# H-00488_-_Card_Slot_Master.net
KiCad netlist of a schematic drawn in Altium Designer
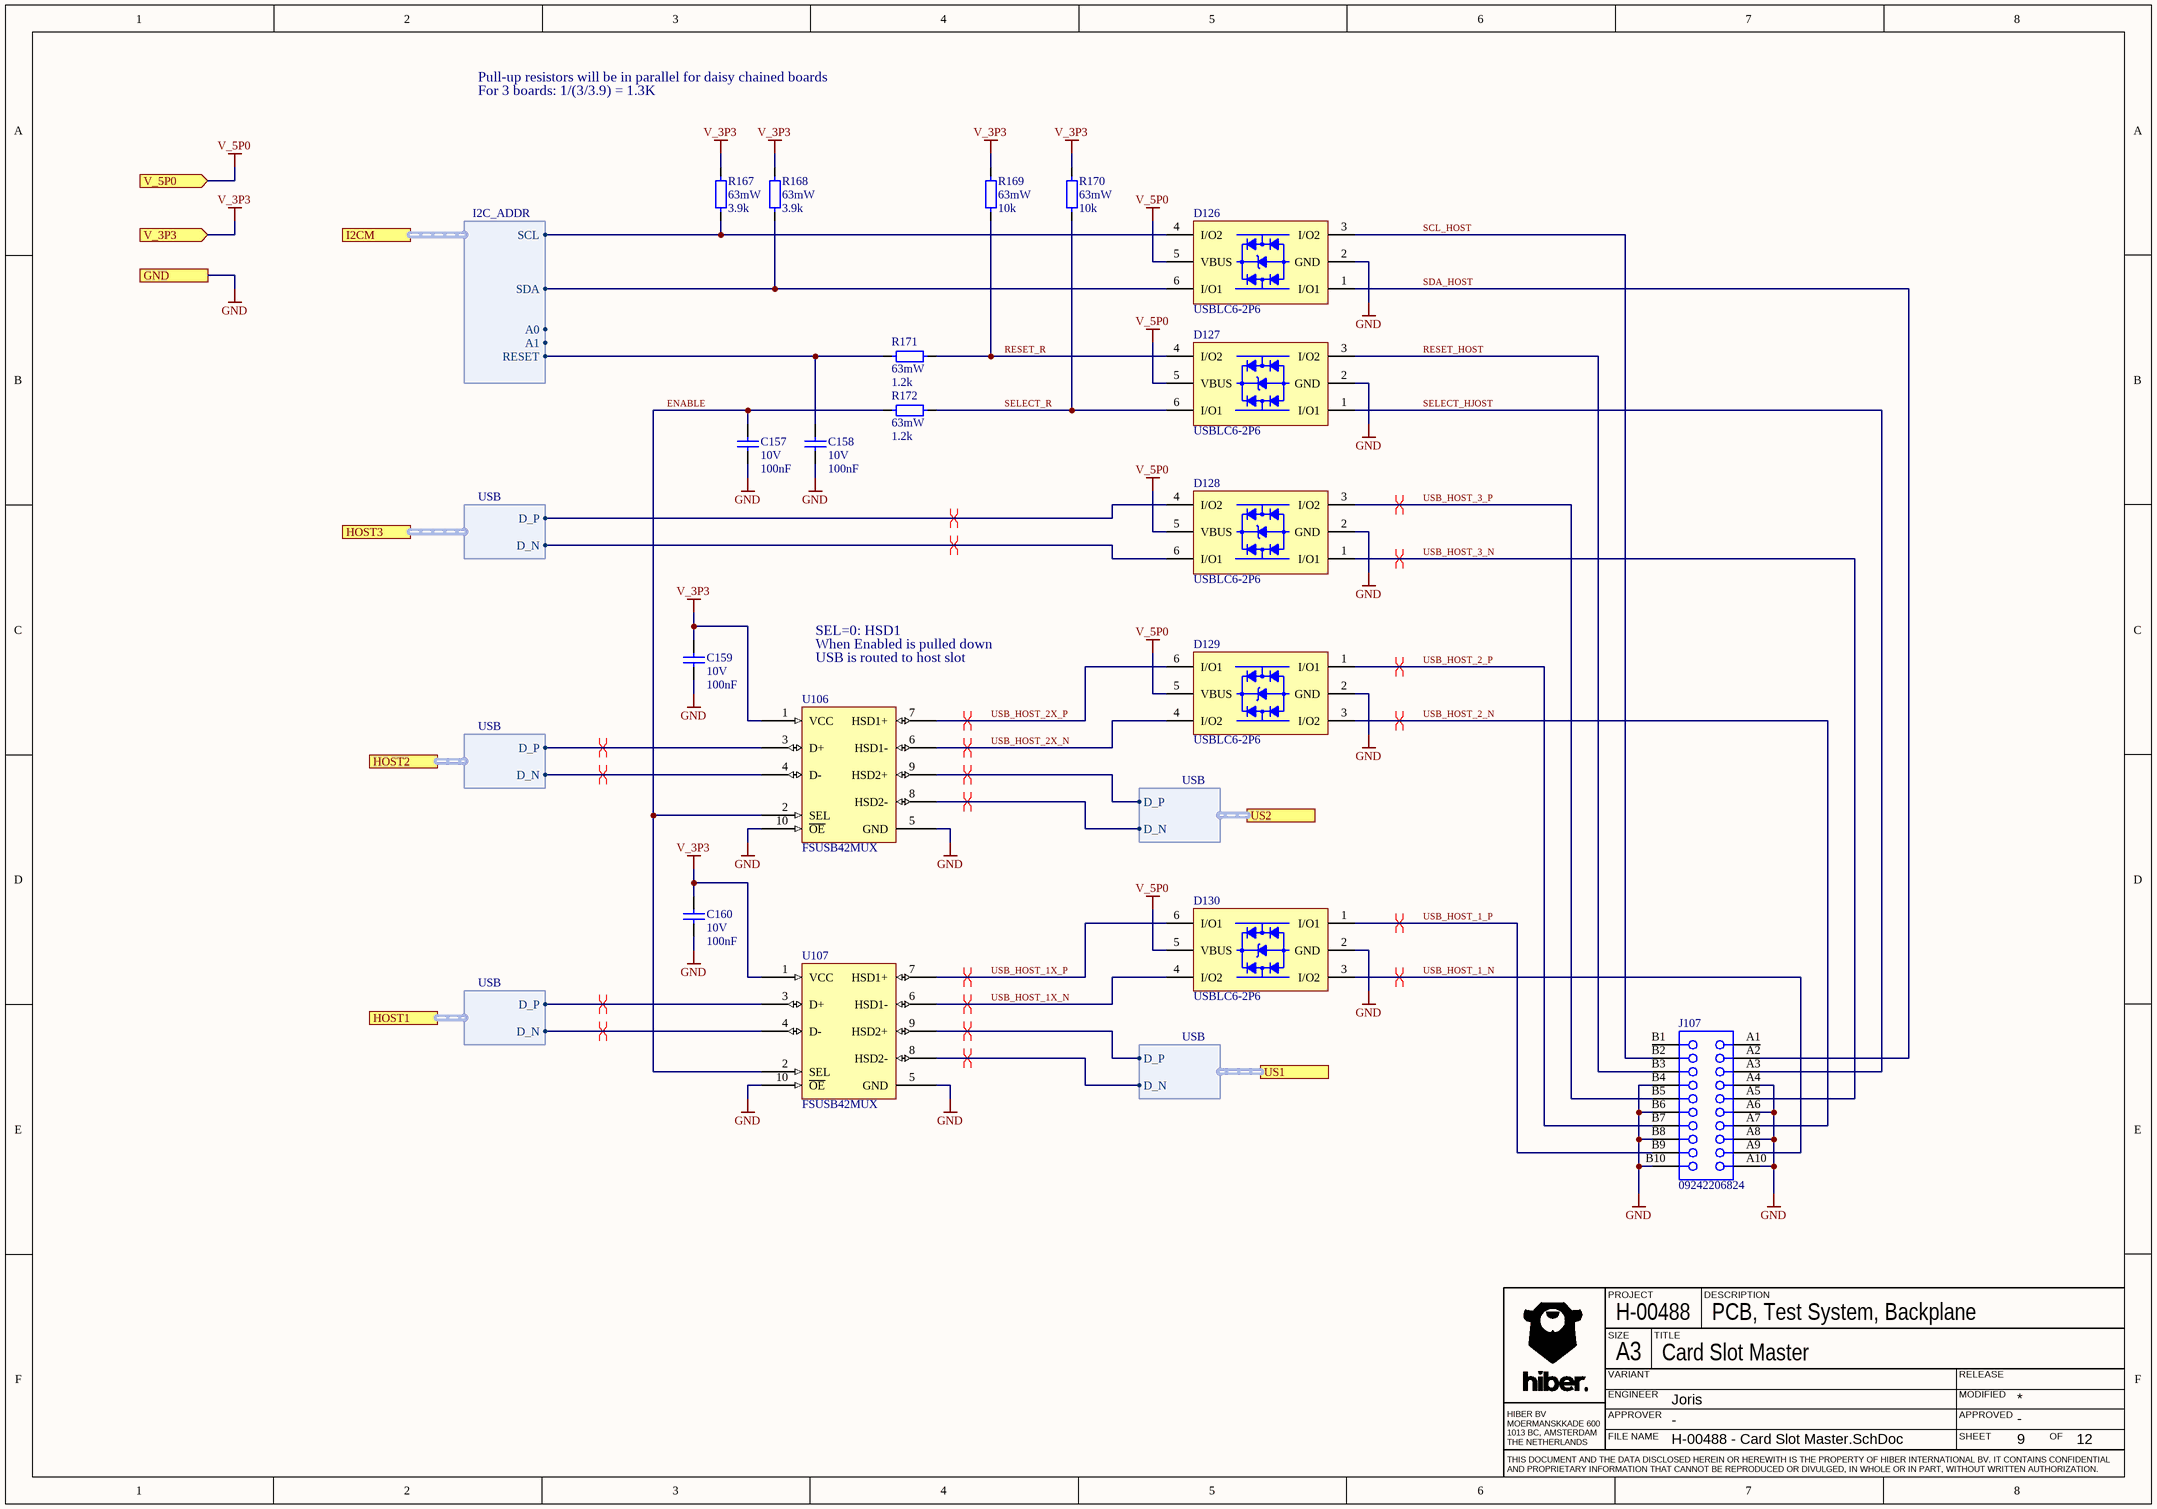
[diagram p0: H-00488 - Card Slot Master.SchDoc]

(export (version "E")
  (design (tool "Eeschema 10.0.6"))
  (components
    (comp (ref "C157")
      (value "100nF")
      (footprint "CAPC100X50X55L30N")
      (description "CAP Standard 0402 (1005) 100,0nF 10V X7R (Standard)")
      (fields
        (field (name "RATED VOLTAGE") "10V")
        (field (name "TOLERANCE") "10%")
        (field (name "Comment") "C0402C104K8RACTU")
      )
      (libsource (lib "Hiber Vault") (part "CAPACITOR"))
    )
    (comp (ref "C158")
      (value "100nF")
      (footprint "CAPC100X50X55L30N")
      (description "CAP Standard 0402 (1005) 100,0nF 10V X7R (Standard)")
      (fields
        (field (name "RATED VOLTAGE") "10V")
        (field (name "TOLERANCE") "10%")
        (field (name "Comment") "C0402C104K8RACTU")
      )
      (libsource (lib "Hiber Vault") (part "CAPACITOR"))
    )
    (comp (ref "C159")
      (value "100nF")
      (footprint "CAPC100X50X55L30N")
      (description "CAP Standard 0402 (1005) 100,0nF 10V X7R (Standard)")
      (fields
        (field (name "RATED VOLTAGE") "10V")
        (field (name "TOLERANCE") "10%")
        (field (name "Comment") "C0402C104K8RACTU")
      )
      (libsource (lib "Hiber Vault") (part "CAPACITOR"))
    )
    (comp (ref "C160")
      (value "100nF")
      (footprint "CAPC100X50X55L30N")
      (description "CAP Standard 0402 (1005) 100,0nF 10V X7R (Standard)")
      (fields
        (field (name "RATED VOLTAGE") "10V")
        (field (name "TOLERANCE") "10%")
        (field (name "Comment") "C0402C104K8RACTU")
      )
      (libsource (lib "Hiber Vault") (part "CAPACITOR"))
    )
    (comp (ref "D126")
      (value "USBLC6-2P6")
      (footprint "DIOSOFL6P50_160X160X95L29X26")
      (description "TVS DIODE 5.25VWM 17VC SOT666")
      (libsource (lib "Hiber") (part "ST_USBLC6-2"))
    )
    (comp (ref "D127")
      (value "USBLC6-2P6")
      (footprint "DIOSOFL6P50_160X160X95L29X26")
      (description "TVS DIODE 5.25VWM 17VC SOT666")
      (libsource (lib "Hiber") (part "ST_USBLC6-2"))
    )
    (comp (ref "D128")
      (value "USBLC6-2P6")
      (footprint "DIOSOFL6P50_160X160X95L29X26")
      (description "TVS DIODE 5.25VWM 17VC SOT666")
      (libsource (lib "Hiber") (part "ST_USBLC6-2"))
    )
    (comp (ref "D129")
      (value "USBLC6-2P6")
      (footprint "DIOSOFL6P50_160X160X95L29X26")
      (description "TVS DIODE 5.25VWM 17VC SOT666")
      (libsource (lib "") (part "ST_USBLC6-2_1"))
    )
    (comp (ref "D130")
      (value "USBLC6-2P6")
      (footprint "DIOSOFL6P50_160X160X95L29X26")
      (description "TVS DIODE 5.25VWM 17VC SOT666")
      (libsource (lib "") (part "ST_USBLC6-2_1"))
    )
    (comp (ref "J107")
      (value "09242206824")
      (footprint "HARTING_09242206824")
      (description "Board Euro Connector")
      (libsource (lib "Hiber") (part "DIN41612-3B-FEMALE"))
    )
    (comp (ref "R167")
      (value "3.9k")
      (footprint "RESC100X50X40L25N")
      (description "RES Standard Thick Film 0402 3K90 ±1% 0,063W")
      (fields
        (field (name "TOLERANCE") "1%")
        (field (name "RATED POWER") "63mW")
        (field (name "Comment") "CRCW04023K90FKED")
      )
      (libsource (lib "Hiber") (part "RESISTOR-2P"))
    )
    (comp (ref "R168")
      (value "3.9k")
      (footprint "RESC100X50X40L25N")
      (description "RES Standard Thick Film 0402 3K90 ±1% 0,063W")
      (fields
        (field (name "TOLERANCE") "1%")
        (field (name "RATED POWER") "63mW")
        (field (name "Comment") "CRCW04023K90FKED")
      )
      (libsource (lib "Hiber") (part "RESISTOR-2P"))
    )
    (comp (ref "R169")
      (value "10k")
      (footprint "RESC100X50X40L25N")
      (description "RES Standard Thick Film 0402 10K0 ±1% 0,063W")
      (fields
        (field (name "TOLERANCE") "1%")
        (field (name "RATED POWER") "63mW")
        (field (name "Comment") "CRCW040210K0FKED")
      )
      (libsource (lib "Hiber") (part "RESISTOR-2P"))
    )
    (comp (ref "R170")
      (value "10k")
      (footprint "RESC100X50X40L25N")
      (description "RES Standard Thick Film 0402 10K0 ±1% 0,063W")
      (fields
        (field (name "TOLERANCE") "1%")
        (field (name "RATED POWER") "63mW")
        (field (name "Comment") "CRCW040210K0FKED")
      )
      (libsource (lib "Hiber") (part "RESISTOR-2P"))
    )
    (comp (ref "R171")
      (value "1.2k")
      (footprint "RESC100X50X40L25N")
      (description "RES Standard Thick Film 0402 1K20 ±1% 0,063W")
      (fields
        (field (name "TOLERANCE") "1%")
        (field (name "RATED POWER") "63mW")
        (field (name "Comment") "CRCW04021K20FKED")
      )
      (libsource (lib "Hiber") (part "RESISTOR-2P"))
    )
    (comp (ref "R172")
      (value "1.2k")
      (footprint "RESC100X50X40L25N")
      (description "RES Standard Thick Film 0402 1K20 ±1% 0,063W")
      (fields
        (field (name "TOLERANCE") "1%")
        (field (name "RATED POWER") "63mW")
        (field (name "Comment") "CRCW04021K20FKED")
      )
      (libsource (lib "Hiber") (part "RESISTOR-2P"))
    )
    (comp (ref "U106")
      (value "FSUSB42MUX")
      (footprint "SOP10P50_300X490X110L55X25")
      (description "IC USB SWITCH DPDT 10MSOP")
      (fields (field (name "VOLTAGE") "4.3V"))
      (libsource (lib "Hiber") (part "FSUSB42MUX"))
    )
    (comp (ref "U107")
      (value "FSUSB42MUX")
      (footprint "SOP10P50_300X490X110L55X25")
      (description "IC USB SWITCH DPDT 10MSOP")
      (fields (field (name "VOLTAGE") "4.3V"))
      (libsource (lib "Hiber") (part "FSUSB42MUX"))
    )
  )
  (nets
    (net (code "3") (name "/ENABLE") (class "Default")
      (node (ref "C157") (pin "1") (pinfunction "1_1") (pintype "passive"))
      (node (ref "R172") (pin "2") (pinfunction "2_2") (pintype "passive"))
      (node (ref "U106") (pin "2") (pinfunction "SEL_2") (pintype "input"))
      (node (ref "U107") (pin "2") (pinfunction "SEL_2") (pintype "input"))
    )
    (net (code "4") (name "/RESET") (class "Default")
      (node (ref "C158") (pin "1") (pinfunction "1_1") (pintype "passive"))
      (node (ref "R171") (pin "2") (pinfunction "2_2") (pintype "passive"))
    )
    (net (code "5") (name "/RESET_HOST") (class "Default")
      (node (ref "D127") (pin "3") (pinfunction "I/O2_3") (pintype "passive"))
      (node (ref "J107") (pin "B3") (pinfunction "B3_B3") (pintype "passive"))
    )
    (net (code "6") (name "/RESET_R") (class "Default")
      (node (ref "D127") (pin "4") (pinfunction "I/O2_4") (pintype "passive"))
      (node (ref "R169") (pin "1") (pinfunction "1_1") (pintype "passive"))
      (node (ref "R171") (pin "1") (pinfunction "1_1") (pintype "passive"))
    )
    (net (code "7") (name "/SCL") (class "Default")
      (node (ref "D126") (pin "4") (pinfunction "I/O2_4") (pintype "passive"))
      (node (ref "R167") (pin "1") (pinfunction "1_1") (pintype "passive"))
    )
    (net (code "8") (name "/SCL_HOST") (class "Default")
      (node (ref "D126") (pin "3") (pinfunction "I/O2_3") (pintype "passive"))
      (node (ref "J107") (pin "B2") (pinfunction "B2_B2") (pintype "passive"))
    )
    (net (code "9") (name "/SDA") (class "Default")
      (node (ref "D126") (pin "6") (pinfunction "I/O1_6") (pintype "passive"))
      (node (ref "R168") (pin "1") (pinfunction "1_1") (pintype "passive"))
    )
    (net (code "10") (name "/SDA_HOST") (class "Default")
      (node (ref "D126") (pin "1") (pinfunction "I/O1_1") (pintype "passive"))
      (node (ref "J107") (pin "A2") (pinfunction "A2_A2") (pintype "passive"))
    )
    (net (code "11") (name "/SELECT_HJOST") (class "Default")
      (node (ref "D127") (pin "1") (pinfunction "I/O1_1") (pintype "passive"))
      (node (ref "J107") (pin "A3") (pinfunction "A3_A3") (pintype "passive"))
    )
    (net (code "12") (name "/SELECT_R") (class "Default")
      (node (ref "D127") (pin "6") (pinfunction "I/O1_6") (pintype "passive"))
      (node (ref "R170") (pin "1") (pinfunction "1_1") (pintype "passive"))
      (node (ref "R172") (pin "1") (pinfunction "1_1") (pintype "passive"))
    )
    (net (code "13") (name "/USB_HOST_1X_N") (class "Default")
      (node (ref "D130") (pin "4") (pinfunction "I/O2_4") (pintype "passive"))
      (node (ref "U107") (pin "6") (pinfunction "HSD1-_6") (pintype "bidirectional"))
    )
    (net (code "14") (name "/USB_HOST_1X_P") (class "Default")
      (node (ref "D130") (pin "6") (pinfunction "I/O1_6") (pintype "passive"))
      (node (ref "U107") (pin "7") (pinfunction "HSD1+_7") (pintype "bidirectional"))
    )
    (net (code "15") (name "/USB_HOST_1_N") (class "Default")
      (node (ref "D130") (pin "3") (pinfunction "I/O2_3") (pintype "passive"))
      (node (ref "J107") (pin "A9") (pinfunction "A9_A9") (pintype "passive"))
    )
    (net (code "16") (name "/USB_HOST_1_P") (class "Default")
      (node (ref "D130") (pin "1") (pinfunction "I/O1_1") (pintype "passive"))
      (node (ref "J107") (pin "B9") (pinfunction "B9_B9") (pintype "passive"))
    )
    (net (code "17") (name "/USB_HOST_2X_N") (class "Default")
      (node (ref "D129") (pin "4") (pinfunction "I/O2_4") (pintype "passive"))
      (node (ref "U106") (pin "6") (pinfunction "HSD1-_6") (pintype "bidirectional"))
    )
    (net (code "18") (name "/USB_HOST_2X_P") (class "Default")
      (node (ref "D129") (pin "6") (pinfunction "I/O1_6") (pintype "passive"))
      (node (ref "U106") (pin "7") (pinfunction "HSD1+_7") (pintype "bidirectional"))
    )
    (net (code "19") (name "/USB_HOST_2_N") (class "Default")
      (node (ref "D129") (pin "3") (pinfunction "I/O2_3") (pintype "passive"))
      (node (ref "J107") (pin "A7") (pinfunction "A7_A7") (pintype "passive"))
    )
    (net (code "20") (name "/USB_HOST_2_P") (class "Default")
      (node (ref "D129") (pin "1") (pinfunction "I/O1_1") (pintype "passive"))
      (node (ref "J107") (pin "B7") (pinfunction "B7_B7") (pintype "passive"))
    )
    (net (code "21") (name "/USB_HOST_3_N") (class "Default")
      (node (ref "D128") (pin "1") (pinfunction "I/O1_1") (pintype "passive"))
      (node (ref "J107") (pin "A5") (pinfunction "A5_A5") (pintype "passive"))
    )
    (net (code "22") (name "/USB_HOST_3_P") (class "Default")
      (node (ref "D128") (pin "3") (pinfunction "I/O2_3") (pintype "passive"))
      (node (ref "J107") (pin "B5") (pinfunction "B5_B5") (pintype "passive"))
    )
    (net (code "25") (name "GND") (class "Default")
      (node (ref "C157") (pin "2") (pinfunction "2_2") (pintype "passive"))
      (node (ref "C158") (pin "2") (pinfunction "2_2") (pintype "passive"))
      (node (ref "C159") (pin "2") (pinfunction "2_2") (pintype "passive"))
      (node (ref "C160") (pin "2") (pinfunction "2_2") (pintype "passive"))
      (node (ref "D126") (pin "2") (pinfunction "GND_2") (pintype "passive"))
      (node (ref "D127") (pin "2") (pinfunction "GND_2") (pintype "passive"))
      (node (ref "D128") (pin "2") (pinfunction "GND_2") (pintype "passive"))
      (node (ref "D129") (pin "2") (pinfunction "GND_2") (pintype "passive"))
      (node (ref "D130") (pin "2") (pinfunction "GND_2") (pintype "passive"))
      (node (ref "J107") (pin "A10") (pinfunction "A10_A10") (pintype "passive"))
      (node (ref "J107") (pin "A4") (pinfunction "A4_A4") (pintype "passive"))
      (node (ref "J107") (pin "A6") (pinfunction "A6_A6") (pintype "passive"))
      (node (ref "J107") (pin "A8") (pinfunction "A8_A8") (pintype "passive"))
      (node (ref "J107") (pin "B10") (pinfunction "B10_B10") (pintype "passive"))
      (node (ref "J107") (pin "B4") (pinfunction "B4_B4") (pintype "passive"))
      (node (ref "J107") (pin "B6") (pinfunction "B6_B6") (pintype "passive"))
      (node (ref "J107") (pin "B8") (pinfunction "B8_B8") (pintype "passive"))
      (node (ref "U106") (pin "10") (pinfunction "~{OE}_10") (pintype "input"))
      (node (ref "U106") (pin "5") (pinfunction "GND_5") (pintype "power_in"))
      (node (ref "U107") (pin "10") (pinfunction "~{OE}_10") (pintype "input"))
      (node (ref "U107") (pin "5") (pinfunction "GND_5") (pintype "power_in"))
    )
    (net (code "26") (name "V_3P3") (class "Default")
      (node (ref "C159") (pin "1") (pinfunction "1_1") (pintype "passive"))
      (node (ref "C160") (pin "1") (pinfunction "1_1") (pintype "passive"))
      (node (ref "R167") (pin "2") (pinfunction "2_2") (pintype "passive"))
      (node (ref "R168") (pin "2") (pinfunction "2_2") (pintype "passive"))
      (node (ref "R169") (pin "2") (pinfunction "2_2") (pintype "passive"))
      (node (ref "R170") (pin "2") (pinfunction "2_2") (pintype "passive"))
      (node (ref "U106") (pin "1") (pinfunction "VCC_1") (pintype "input"))
      (node (ref "U107") (pin "1") (pinfunction "VCC_1") (pintype "input"))
    )
    (net (code "27") (name "V_5P0") (class "Default")
      (node (ref "D126") (pin "5") (pinfunction "VBUS_5") (pintype "passive"))
      (node (ref "D127") (pin "5") (pinfunction "VBUS_5") (pintype "passive"))
      (node (ref "D128") (pin "5") (pinfunction "VBUS_5") (pintype "passive"))
      (node (ref "D129") (pin "5") (pinfunction "VBUS_5") (pintype "passive"))
      (node (ref "D130") (pin "5") (pinfunction "VBUS_5") (pintype "passive"))
    )
    (net (code "28") (name "unconnected-(D128-I{slash}O1-Pad6)") (class "Default")
      (node (ref "D128") (pin "6") (pinfunction "I/O1_6") (pintype "passive"))
    )
    (net (code "29") (name "unconnected-(D128-I{slash}O2-Pad4)") (class "Default")
      (node (ref "D128") (pin "4") (pinfunction "I/O2_4") (pintype "passive"))
    )
    (net (code "30") (name "unconnected-(J107-PadA1)") (class "Default")
      (node (ref "J107") (pin "A1") (pinfunction "A1_A1") (pintype "passive"))
    )
    (net (code "31") (name "unconnected-(J107-PadB1)") (class "Default")
      (node (ref "J107") (pin "B1") (pinfunction "B1_B1") (pintype "passive"))
    )
    (net (code "32") (name "unconnected-(U106-D+-Pad3)") (class "Default")
      (node (ref "U106") (pin "3") (pinfunction "D+_3") (pintype "bidirectional"))
    )
    (net (code "33") (name "unconnected-(U106-D--Pad4)") (class "Default")
      (node (ref "U106") (pin "4") (pinfunction "D-_4") (pintype "bidirectional"))
    )
    (net (code "34") (name "unconnected-(U106-HSD2+-Pad9)") (class "Default")
      (node (ref "U106") (pin "9") (pinfunction "HSD2+_9") (pintype "bidirectional"))
    )
    (net (code "35") (name "unconnected-(U106-HSD2--Pad8)") (class "Default")
      (node (ref "U106") (pin "8") (pinfunction "HSD2-_8") (pintype "bidirectional"))
    )
    (net (code "36") (name "unconnected-(U107-D+-Pad3)") (class "Default")
      (node (ref "U107") (pin "3") (pinfunction "D+_3") (pintype "bidirectional"))
    )
    (net (code "37") (name "unconnected-(U107-D--Pad4)") (class "Default")
      (node (ref "U107") (pin "4") (pinfunction "D-_4") (pintype "bidirectional"))
    )
    (net (code "38") (name "unconnected-(U107-HSD2+-Pad9)") (class "Default")
      (node (ref "U107") (pin "9") (pinfunction "HSD2+_9") (pintype "bidirectional"))
    )
    (net (code "39") (name "unconnected-(U107-HSD2--Pad8)") (class "Default")
      (node (ref "U107") (pin "8") (pinfunction "HSD2-_8") (pintype "bidirectional"))
    )
  )
)
